# Omnibot_battery_module.net
KiCad netlist of a schematic drawn in EAGLE
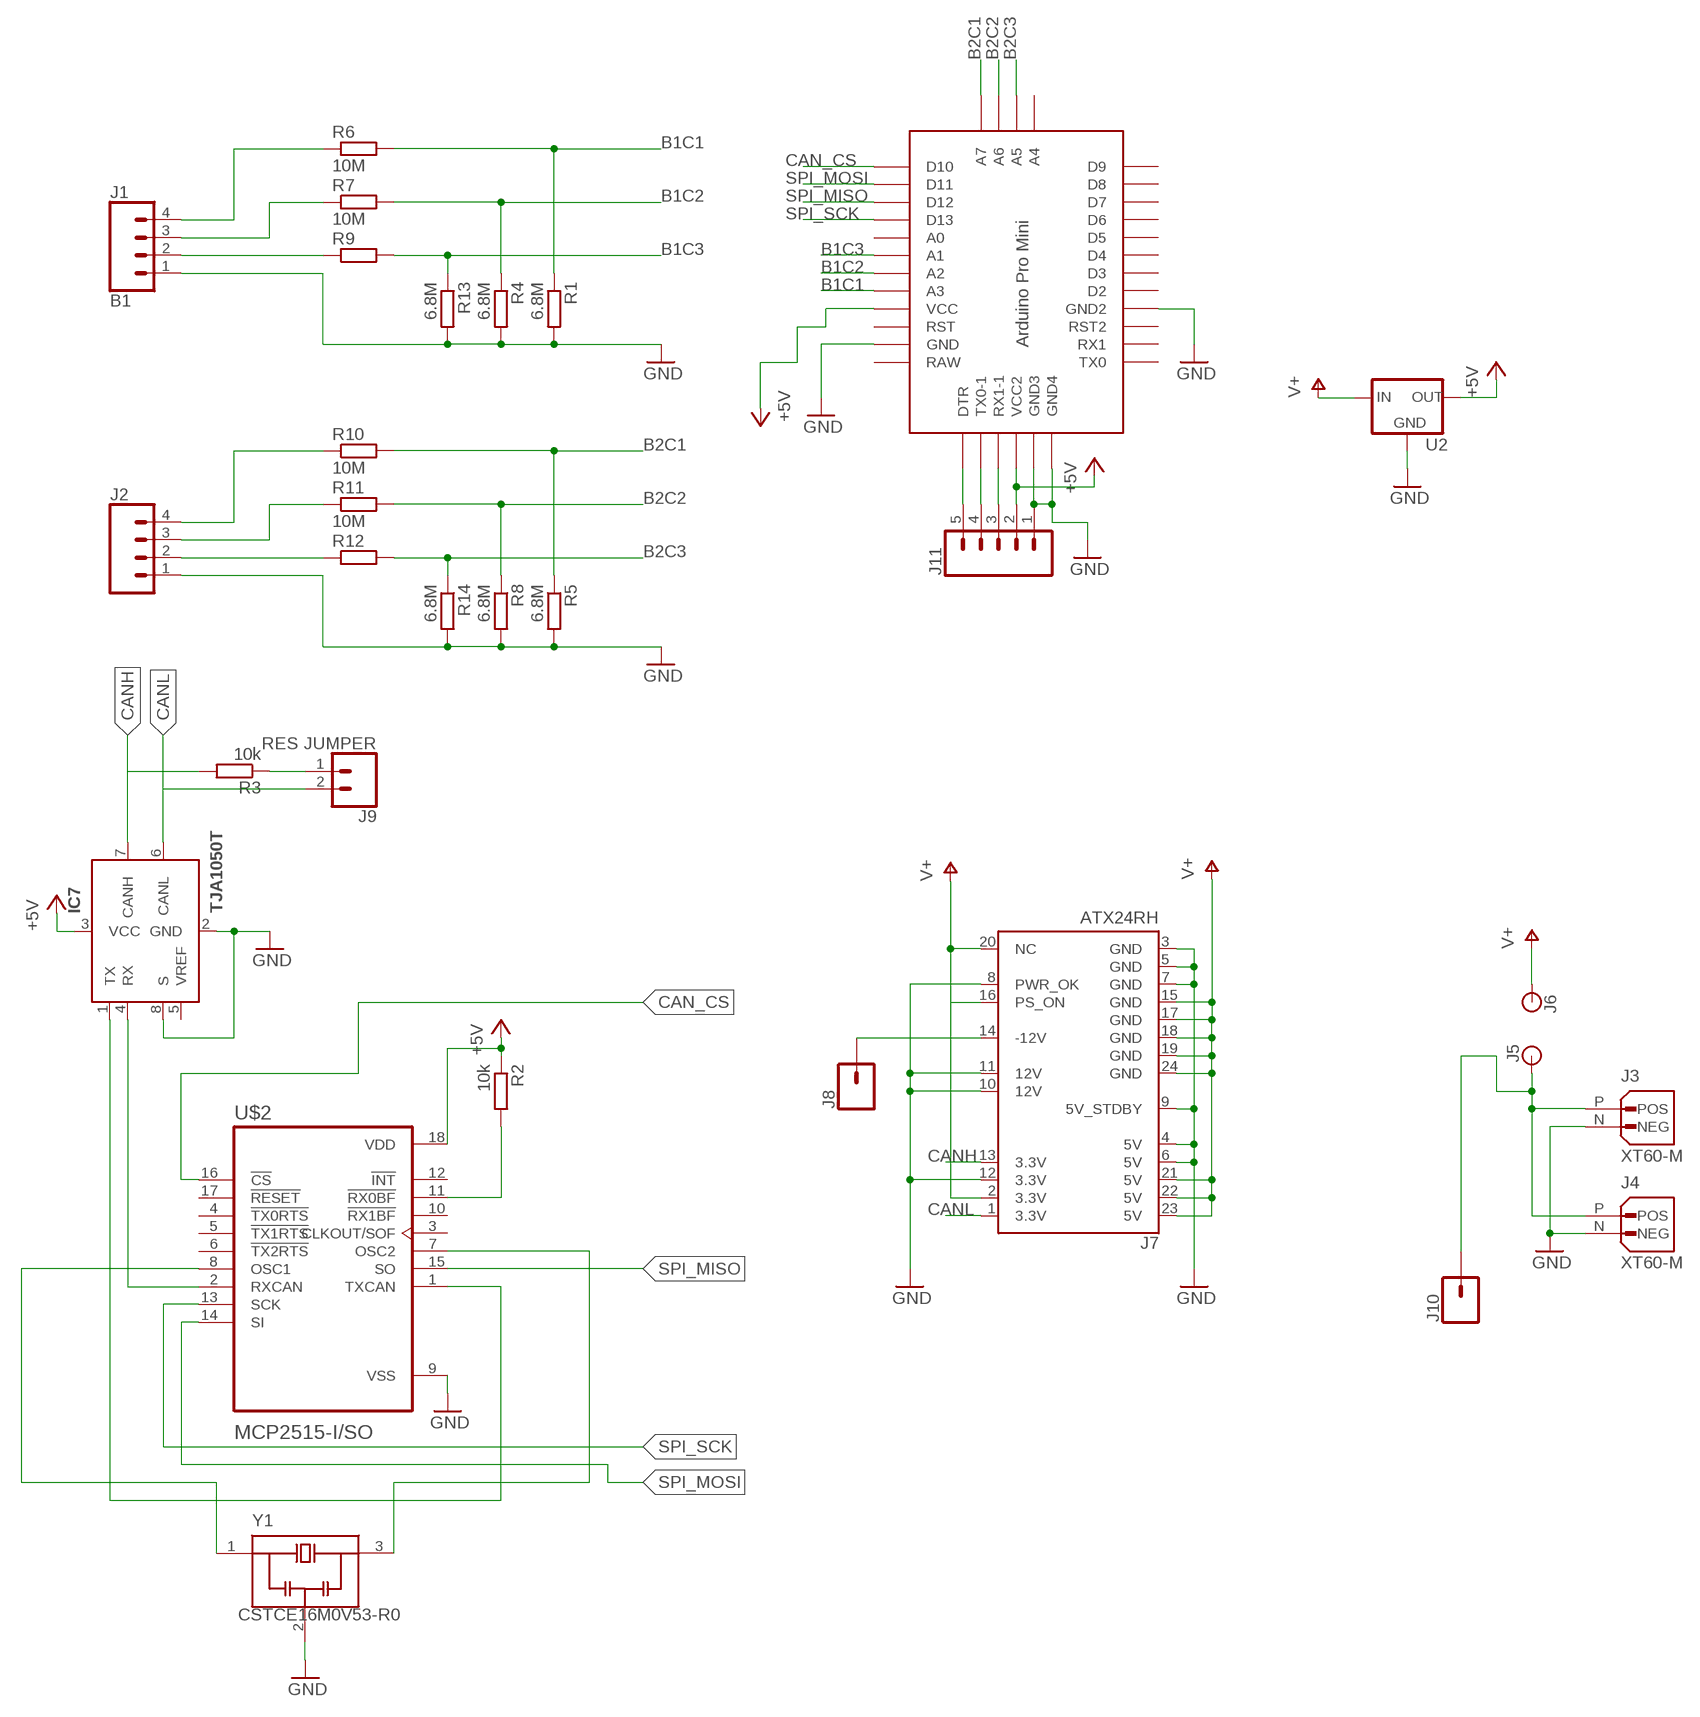
[diagram p0: schematic, sheet 1]

(export (version "E")
  (design (tool "Eeschema 10.0.6"))
  (components
    (comp (ref "IC7")
      (value "TJA1050T")
      (footprint "eagle-import:SOIC8")
      (fields (field (name "MF") "NXP"))
      (libsource (lib "eagle-import") (part "TJA1050T"))
    )
    (comp (ref "J1")
      (value "B1")
      (footprint "eagle-import:MOLEX-1X4")
      (libsource (lib "eagle-import") (part "CONN_04POLAR"))
    )
    (comp (ref "J2")
      (value "CONN_04POLAR")
      (footprint "eagle-import:MOLEX-1X4")
      (libsource (lib "eagle-import") (part "CONN_04POLAR"))
    )
    (comp (ref "J3")
      (value "XT60-M")
      (footprint "eagle-import:AMASS_XT60-M")
      (fields (field (name "MF") "AMASS"))
      (libsource (lib "eagle-import") (part "XT60-M"))
    )
    (comp (ref "J4")
      (value "XT60-M")
      (footprint "eagle-import:AMASS_XT60-M")
      (fields (field (name "MF") "AMASS"))
      (libsource (lib "eagle-import") (part "XT60-M"))
    )
    (comp (ref "J5")
      (value "BANANA_CONN")
      (footprint "eagle-import:BANANA_CONN")
      (libsource (lib "eagle-import") (part "BANANA_CONN"))
    )
    (comp (ref "J6")
      (value "BANANA_CONN")
      (footprint "eagle-import:BANANA_CONN")
      (libsource (lib "eagle-import") (part "BANANA_CONN"))
    )
    (comp (ref "J7")
      (value "ATX24RH")
      (footprint "eagle-import:ATX24_RIGHT_ANGLE")
      (libsource (lib "eagle-import") (part "ATX24RH"))
    )
    (comp (ref "J8")
      (value "CONN_01")
      (footprint "eagle-import:1X01")
      (libsource (lib "eagle-import") (part "CONN_01"))
    )
    (comp (ref "J9")
      (value "RES JUMPER")
      (footprint "eagle-import:1X02")
      (libsource (lib "eagle-import") (part "CONN_02"))
    )
    (comp (ref "J10")
      (value "CONN_01")
      (footprint "eagle-import:1X01")
      (libsource (lib "eagle-import") (part "CONN_01"))
    )
    (comp (ref "J11")
      (value "CONN_05PTH")
      (footprint "eagle-import:1X05")
      (libsource (lib "eagle-import") (part "CONN_05PTH"))
    )
    (comp (ref "R1")
      (value "6.8M")
      (footprint "eagle-import:M0805")
      (libsource (lib "eagle-import") (part "R-EU_M0805"))
    )
    (comp (ref "R2")
      (value "10k")
      (footprint "eagle-import:R0805")
      (libsource (lib "eagle-import") (part "R-EU_R0805"))
    )
    (comp (ref "R3")
      (value "10k")
      (footprint "eagle-import:R0805")
      (libsource (lib "eagle-import") (part "R-EU_R0805"))
    )
    (comp (ref "R4")
      (value "6.8M")
      (footprint "eagle-import:M0805")
      (libsource (lib "eagle-import") (part "R-EU_M0805"))
    )
    (comp (ref "R5")
      (value "6.8M")
      (footprint "eagle-import:M0805")
      (libsource (lib "eagle-import") (part "R-EU_M0805"))
    )
    (comp (ref "R6")
      (value "10M")
      (footprint "eagle-import:M0805")
      (libsource (lib "eagle-import") (part "R-EU_M0805"))
    )
    (comp (ref "R7")
      (value "10M")
      (footprint "eagle-import:M0805")
      (libsource (lib "eagle-import") (part "R-EU_M0805"))
    )
    (comp (ref "R8")
      (value "6.8M")
      (footprint "eagle-import:M0805")
      (libsource (lib "eagle-import") (part "R-EU_M0805"))
    )
    (comp (ref "R9")
      (value "10M")
      (footprint "eagle-import:M0805")
      (libsource (lib "eagle-import") (part "R-EU_M0805"))
    )
    (comp (ref "R10")
      (value "10M")
      (footprint "eagle-import:M0805")
      (libsource (lib "eagle-import") (part "R-EU_M0805"))
    )
    (comp (ref "R11")
      (value "10M")
      (footprint "eagle-import:M0805")
      (libsource (lib "eagle-import") (part "R-EU_M0805"))
    )
    (comp (ref "R12")
      (value "10M")
      (footprint "eagle-import:M0805")
      (libsource (lib "eagle-import") (part "R-EU_M0805"))
    )
    (comp (ref "R13")
      (value "6.8M")
      (footprint "eagle-import:M0805")
      (libsource (lib "eagle-import") (part "R-EU_M0805"))
    )
    (comp (ref "R14")
      (value "6.8M")
      (footprint "eagle-import:M0805")
      (libsource (lib "eagle-import") (part "R-EU_M0805"))
    )
    (comp (ref "U$1")
      (value "PRO-MINI")
      (footprint "eagle-import:PRO-MINI")
      (libsource (lib "eagle-import") (part "PRO-MINI"))
    )
    (comp (ref "U$2")
      (value "MCP2515-I/SO")
      (footprint "eagle-import:SOIC127P1030X265-18N")
      (fields (field (name "MF") "Microchip"))
      (libsource (lib "eagle-import") (part "MCP2515-I/SO"))
    )
    (comp (ref "U2")
      (value "V_REG_78XX-TO-220")
      (footprint "eagle-import:TO-220-ALT")
      (libsource (lib "eagle-import") (part "V_REG_78XX-TO-220"))
    )
    (comp (ref "Y1")
      (value "CSTCE16M0V53-R0")
      (footprint "eagle-import:OSC_CSTCE16M0V53-R0")
      (fields (field (name "MF") "Murata"))
      (libsource (lib "eagle-import") (part "CSTCE16M0V53-R0"))
    )
  )
  (nets
    (net (code "1") (name "+5V") (class "Default")
      (node (ref "IC7") (pin "3") (pinfunction "VCC_3") (pintype "input"))
      (node (ref "J11") (pin "2") (pinfunction "2_2") (pintype "passive"))
      (node (ref "R2") (pin "1") (pinfunction "1_1") (pintype "passive"))
      (node (ref "U$1") (pin "VCC") (pinfunction "VCC_VCC") (pintype "bidirectional"))
      (node (ref "U$1") (pin "VCC1") (pinfunction "VCC2_VCC1") (pintype "bidirectional"))
      (node (ref "U$2") (pin "18") (pinfunction "VDD_18") (pintype "power_in"))
      (node (ref "U2") (pin "OUT") (pinfunction "OUT_OUT") (pintype "passive"))
    )
    (net (code "2") (name "/B1C1") (class "Default")
      (node (ref "R1") (pin "1") (pinfunction "1_1") (pintype "passive"))
      (node (ref "R6") (pin "2") (pinfunction "2_2") (pintype "passive"))
      (node (ref "U$1") (pin "A3") (pinfunction "A3_A3") (pintype "bidirectional"))
    )
    (net (code "3") (name "/B1C2") (class "Default")
      (node (ref "R4") (pin "1") (pinfunction "1_1") (pintype "passive"))
      (node (ref "R7") (pin "2") (pinfunction "2_2") (pintype "passive"))
      (node (ref "U$1") (pin "A2") (pinfunction "A2_A2") (pintype "bidirectional"))
    )
    (net (code "4") (name "/B1C3") (class "Default")
      (node (ref "R13") (pin "1") (pinfunction "1_1") (pintype "passive"))
      (node (ref "R9") (pin "2") (pinfunction "2_2") (pintype "passive"))
      (node (ref "U$1") (pin "A1") (pinfunction "A1_A1") (pintype "bidirectional"))
    )
    (net (code "5") (name "/B2C1") (class "Default")
      (node (ref "R10") (pin "2") (pinfunction "2_2") (pintype "passive"))
      (node (ref "R5") (pin "1") (pinfunction "1_1") (pintype "passive"))
      (node (ref "U$1") (pin "A7") (pinfunction "A7_A7") (pintype "bidirectional"))
    )
    (net (code "6") (name "/B2C2") (class "Default")
      (node (ref "R11") (pin "2") (pinfunction "2_2") (pintype "passive"))
      (node (ref "R8") (pin "1") (pinfunction "1_1") (pintype "passive"))
      (node (ref "U$1") (pin "A6") (pinfunction "A6_A6") (pintype "bidirectional"))
    )
    (net (code "7") (name "/B2C3") (class "Default")
      (node (ref "R12") (pin "2") (pinfunction "2_2") (pintype "passive"))
      (node (ref "R14") (pin "1") (pinfunction "1_1") (pintype "passive"))
      (node (ref "U$1") (pin "A5") (pinfunction "A5_A5") (pintype "bidirectional"))
    )
    (net (code "8") (name "/RAW") (class "Default")
      (node (ref "U$1") (pin "RAW") (pinfunction "RAW_RAW") (pintype "power_in"))
    )
    (net (code "9") (name "CANH") (class "Default")
      (node (ref "IC7") (pin "7") (pinfunction "CANH_7") (pintype "bidirectional"))
      (node (ref "J7") (pin "13") (pinfunction "3.3V_13") (pintype "bidirectional"))
      (node (ref "R3") (pin "2") (pinfunction "2_2") (pintype "passive"))
    )
    (net (code "10") (name "CANL") (class "Default")
      (node (ref "IC7") (pin "6") (pinfunction "CANL_6") (pintype "bidirectional"))
      (node (ref "J7") (pin "1") (pinfunction "3.3V_1") (pintype "bidirectional"))
      (node (ref "J9") (pin "2") (pinfunction "2_2") (pintype "passive"))
    )
    (net (code "11") (name "CAN_CS") (class "Default")
      (node (ref "U$1") (pin "D10") (pinfunction "D10_D10") (pintype "bidirectional"))
      (node (ref "U$2") (pin "16") (pinfunction "~{CS}_16") (pintype "input"))
    )
    (net (code "12") (name "GND") (class "Default")
      (node (ref "IC7") (pin "2") (pinfunction "GND_2") (pintype "power_in"))
      (node (ref "IC7") (pin "8") (pinfunction "S_8") (pintype "input"))
      (node (ref "J1") (pin "1") (pinfunction "1_1") (pintype "passive"))
      (node (ref "J11") (pin "1") (pinfunction "1_1") (pintype "passive"))
      (node (ref "J2") (pin "1") (pinfunction "1_1") (pintype "passive"))
      (node (ref "J3") (pin "N") (pinfunction "NEG_N") (pintype "passive"))
      (node (ref "J4") (pin "N") (pinfunction "NEG_N") (pintype "passive"))
      (node (ref "J7") (pin "10") (pinfunction "12V_10") (pintype "bidirectional"))
      (node (ref "J7") (pin "11") (pinfunction "12V_11") (pintype "bidirectional"))
      (node (ref "J7") (pin "12") (pinfunction "3.3V_12") (pintype "bidirectional"))
      (node (ref "J7") (pin "3") (pinfunction "GND_3") (pintype "bidirectional"))
      (node (ref "J7") (pin "4") (pinfunction "5V_4") (pintype "bidirectional"))
      (node (ref "J7") (pin "5") (pinfunction "GND_5") (pintype "bidirectional"))
      (node (ref "J7") (pin "6") (pinfunction "5V_6") (pintype "bidirectional"))
      (node (ref "J7") (pin "7") (pinfunction "GND_7") (pintype "bidirectional"))
      (node (ref "J7") (pin "8") (pinfunction "PWR_OK_8") (pintype "bidirectional"))
      (node (ref "J7") (pin "9") (pinfunction "5V_STDBY_9") (pintype "bidirectional"))
      (node (ref "R1") (pin "2") (pinfunction "2_2") (pintype "passive"))
      (node (ref "R13") (pin "2") (pinfunction "2_2") (pintype "passive"))
      (node (ref "R14") (pin "2") (pinfunction "2_2") (pintype "passive"))
      (node (ref "R4") (pin "2") (pinfunction "2_2") (pintype "passive"))
      (node (ref "R5") (pin "2") (pinfunction "2_2") (pintype "passive"))
      (node (ref "R8") (pin "2") (pinfunction "2_2") (pintype "passive"))
      (node (ref "U$1") (pin "GND") (pinfunction "GND_GND") (pintype "input"))
      (node (ref "U$1") (pin "GND1") (pinfunction "GND2_GND1") (pintype "bidirectional"))
      (node (ref "U$1") (pin "GND2") (pinfunction "GND4_GND2") (pintype "bidirectional"))
      (node (ref "U$1") (pin "GND3") (pinfunction "GND3_GND3") (pintype "bidirectional"))
      (node (ref "U$2") (pin "9") (pinfunction "VSS_9") (pintype "power_in"))
      (node (ref "U2") (pin "GND") (pinfunction "GND_GND") (pintype "input"))
      (node (ref "Y1") (pin "2") (pinfunction "GND_2") (pintype "power_in"))
    )
    (net (code "13") (name "Net-(IC7-RX)") (class "Default")
      (node (ref "IC7") (pin "4") (pinfunction "RX_4") (pintype "output"))
      (node (ref "U$2") (pin "2") (pinfunction "RXCAN_2") (pintype "input"))
    )
    (net (code "14") (name "Net-(IC7-TX)") (class "Default")
      (node (ref "IC7") (pin "1") (pinfunction "TX_1") (pintype "input"))
      (node (ref "U$2") (pin "1") (pinfunction "TXCAN_1") (pintype "output"))
    )
    (net (code "15") (name "Net-(J1-Pad2)") (class "Default")
      (node (ref "J1") (pin "2") (pinfunction "2_2") (pintype "passive"))
      (node (ref "R9") (pin "1") (pinfunction "1_1") (pintype "passive"))
    )
    (net (code "16") (name "Net-(J1-Pad3)") (class "Default")
      (node (ref "J1") (pin "3") (pinfunction "3_3") (pintype "passive"))
      (node (ref "R7") (pin "1") (pinfunction "1_1") (pintype "passive"))
    )
    (net (code "17") (name "Net-(J1-Pad4)") (class "Default")
      (node (ref "J1") (pin "4") (pinfunction "4_4") (pintype "passive"))
      (node (ref "R6") (pin "1") (pinfunction "1_1") (pintype "passive"))
    )
    (net (code "18") (name "Net-(J2-Pad2)") (class "Default")
      (node (ref "J2") (pin "2") (pinfunction "2_2") (pintype "passive"))
      (node (ref "R12") (pin "1") (pinfunction "1_1") (pintype "passive"))
    )
    (net (code "19") (name "Net-(J2-Pad3)") (class "Default")
      (node (ref "J2") (pin "3") (pinfunction "3_3") (pintype "passive"))
      (node (ref "R11") (pin "1") (pinfunction "1_1") (pintype "passive"))
    )
    (net (code "20") (name "Net-(J2-Pad4)") (class "Default")
      (node (ref "J2") (pin "4") (pinfunction "4_4") (pintype "passive"))
      (node (ref "R10") (pin "1") (pinfunction "1_1") (pintype "passive"))
    )
    (net (code "21") (name "Net-(J3-POS)") (class "Default")
      (node (ref "J10") (pin "1") (pinfunction "1_1") (pintype "passive"))
      (node (ref "J3") (pin "P") (pinfunction "POS_P") (pintype "passive"))
      (node (ref "J4") (pin "P") (pinfunction "POS_P") (pintype "passive"))
      (node (ref "J5") (pin "P$1") (pinfunction "1_P$1") (pintype "passive"))
    )
    (net (code "22") (name "Net-(J7--12V)") (class "Default")
      (node (ref "J7") (pin "14") (pinfunction "-12V_14") (pintype "bidirectional"))
      (node (ref "J8") (pin "1") (pinfunction "1_1") (pintype "passive"))
    )
    (net (code "23") (name "Net-(J9-Pad1)") (class "Default")
      (node (ref "J9") (pin "1") (pinfunction "1_1") (pintype "passive"))
      (node (ref "R3") (pin "1") (pinfunction "1_1") (pintype "passive"))
    )
    (net (code "24") (name "Net-(J11-Pad3)") (class "Default")
      (node (ref "J11") (pin "3") (pinfunction "3_3") (pintype "passive"))
      (node (ref "U$1") (pin "RX1-1") (pinfunction "RX1-1_RX1-1") (pintype "bidirectional"))
    )
    (net (code "25") (name "Net-(J11-Pad4)") (class "Default")
      (node (ref "J11") (pin "4") (pinfunction "4_4") (pintype "passive"))
      (node (ref "U$1") (pin "TX0-1") (pinfunction "TX0-1_TX0-1") (pintype "bidirectional"))
    )
    (net (code "26") (name "Net-(J11-Pad5)") (class "Default")
      (node (ref "J11") (pin "5") (pinfunction "5_5") (pintype "passive"))
      (node (ref "U$1") (pin "DTR") (pinfunction "DTR_DTR") (pintype "bidirectional"))
    )
    (net (code "27") (name "Net-(U$2-OSC1)") (class "Default")
      (node (ref "U$2") (pin "8") (pinfunction "OSC1_8") (pintype "input"))
      (node (ref "Y1") (pin "1") (pinfunction "IN_1") (pintype "input"))
    )
    (net (code "28") (name "Net-(U$2-OSC2)") (class "Default")
      (node (ref "U$2") (pin "7") (pinfunction "OSC2_7") (pintype "output"))
      (node (ref "Y1") (pin "3") (pinfunction "OUT_3") (pintype "output"))
    )
    (net (code "29") (name "Net-(U$2-~{RX0BF})") (class "Default")
      (node (ref "R2") (pin "2") (pinfunction "2_2") (pintype "passive"))
      (node (ref "U$2") (pin "11") (pinfunction "~{RX0BF}_11") (pintype "output"))
    )
    (net (code "30") (name "SPI_MISO") (class "Default")
      (node (ref "U$1") (pin "D12") (pinfunction "D12_D12") (pintype "bidirectional"))
      (node (ref "U$2") (pin "15") (pinfunction "SO_15") (pintype "output"))
    )
    (net (code "31") (name "SPI_MOSI") (class "Default")
      (node (ref "U$1") (pin "D11") (pinfunction "D11_D11") (pintype "bidirectional"))
      (node (ref "U$2") (pin "14") (pinfunction "SI_14") (pintype "input"))
    )
    (net (code "32") (name "SPI_SCK") (class "Default")
      (node (ref "U$1") (pin "D13") (pinfunction "D13_D13") (pintype "bidirectional"))
      (node (ref "U$2") (pin "13") (pinfunction "SCK_13") (pintype "input"))
    )
    (net (code "33") (name "V+") (class "Default")
      (node (ref "J6") (pin "P$1") (pinfunction "1_P$1") (pintype "passive"))
      (node (ref "J7") (pin "15") (pinfunction "GND_15") (pintype "bidirectional"))
      (node (ref "J7") (pin "16") (pinfunction "PS_ON_16") (pintype "bidirectional"))
      (node (ref "J7") (pin "17") (pinfunction "GND_17") (pintype "bidirectional"))
      (node (ref "J7") (pin "18") (pinfunction "GND_18") (pintype "bidirectional"))
      (node (ref "J7") (pin "19") (pinfunction "GND_19") (pintype "bidirectional"))
      (node (ref "J7") (pin "2") (pinfunction "3.3V_2") (pintype "bidirectional"))
      (node (ref "J7") (pin "20") (pinfunction "NC_20") (pintype "bidirectional"))
      (node (ref "J7") (pin "21") (pinfunction "5V_21") (pintype "bidirectional"))
      (node (ref "J7") (pin "22") (pinfunction "5V_22") (pintype "bidirectional"))
      (node (ref "J7") (pin "23") (pinfunction "5V_23") (pintype "bidirectional"))
      (node (ref "J7") (pin "24") (pinfunction "GND_24") (pintype "bidirectional"))
      (node (ref "U2") (pin "IN") (pinfunction "IN_IN") (pintype "input"))
    )
    (net (code "34") (name "unconnected-(IC7-VREF-Pad5)") (class "Default")
      (node (ref "IC7") (pin "5") (pinfunction "VREF_5") (pintype "output"))
    )
    (net (code "35") (name "unconnected-(U$1-PadA0)") (class "Default")
      (node (ref "U$1") (pin "A0") (pinfunction "A0_A0") (pintype "bidirectional"))
    )
    (net (code "36") (name "unconnected-(U$1-PadA4)") (class "Default")
      (node (ref "U$1") (pin "A4") (pinfunction "A4_A4") (pintype "bidirectional"))
    )
    (net (code "37") (name "unconnected-(U$1-PadD2)") (class "Default")
      (node (ref "U$1") (pin "D2") (pinfunction "D2_D2") (pintype "bidirectional"))
    )
    (net (code "38") (name "unconnected-(U$1-PadD3)") (class "Default")
      (node (ref "U$1") (pin "D3") (pinfunction "D3_D3") (pintype "bidirectional"))
    )
    (net (code "39") (name "unconnected-(U$1-PadD4)") (class "Default")
      (node (ref "U$1") (pin "D4") (pinfunction "D4_D4") (pintype "bidirectional"))
    )
    (net (code "40") (name "unconnected-(U$1-PadD5)") (class "Default")
      (node (ref "U$1") (pin "D5") (pinfunction "D5_D5") (pintype "bidirectional"))
    )
    (net (code "41") (name "unconnected-(U$1-PadD6)") (class "Default")
      (node (ref "U$1") (pin "D6") (pinfunction "D6_D6") (pintype "bidirectional"))
    )
    (net (code "42") (name "unconnected-(U$1-PadD7)") (class "Default")
      (node (ref "U$1") (pin "D7") (pinfunction "D7_D7") (pintype "bidirectional"))
    )
    (net (code "43") (name "unconnected-(U$1-PadD8)") (class "Default")
      (node (ref "U$1") (pin "D8") (pinfunction "D8_D8") (pintype "bidirectional"))
    )
    (net (code "44") (name "unconnected-(U$1-PadD9)") (class "Default")
      (node (ref "U$1") (pin "D9") (pinfunction "D9_D9") (pintype "bidirectional"))
    )
    (net (code "45") (name "unconnected-(U$1-PadRST)") (class "Default")
      (node (ref "U$1") (pin "RST") (pinfunction "RST_RST") (pintype "bidirectional"))
    )
    (net (code "46") (name "unconnected-(U$1-PadRX1)") (class "Default")
      (node (ref "U$1") (pin "RX1") (pinfunction "RX1_RX1") (pintype "bidirectional"))
    )
    (net (code "47") (name "unconnected-(U$1-PadTX0)") (class "Default")
      (node (ref "U$1") (pin "TX0") (pinfunction "TX0_TX0") (pintype "bidirectional"))
    )
    (net (code "48") (name "unconnected-(U$1-RST2-PadRST1)") (class "Default")
      (node (ref "U$1") (pin "RST1") (pinfunction "RST2_RST1") (pintype "bidirectional"))
    )
    (net (code "49") (name "unconnected-(U$2-CLKOUT{slash}SOF-Pad3)") (class "Default")
      (node (ref "U$2") (pin "3") (pinfunction "CLKOUT/SOF_3") (pintype "output"))
    )
    (net (code "50") (name "unconnected-(U$2-~{INT}-Pad12)") (class "Default")
      (node (ref "U$2") (pin "12") (pinfunction "~{INT}_12") (pintype "output"))
    )
    (net (code "51") (name "unconnected-(U$2-~{RESET}-Pad17)") (class "Default")
      (node (ref "U$2") (pin "17") (pinfunction "~{RESET}_17") (pintype "input"))
    )
    (net (code "52") (name "unconnected-(U$2-~{RX1BF}-Pad10)") (class "Default")
      (node (ref "U$2") (pin "10") (pinfunction "~{RX1BF}_10") (pintype "output"))
    )
    (net (code "53") (name "unconnected-(U$2-~{TX0RTS}-Pad4)") (class "Default")
      (node (ref "U$2") (pin "4") (pinfunction "~{TX0RTS}_4") (pintype "input"))
    )
    (net (code "54") (name "unconnected-(U$2-~{TX1RTS}-Pad5)") (class "Default")
      (node (ref "U$2") (pin "5") (pinfunction "~{TX1RTS}_5") (pintype "input"))
    )
    (net (code "55") (name "unconnected-(U$2-~{TX2RTS}-Pad6)") (class "Default")
      (node (ref "U$2") (pin "6") (pinfunction "~{TX2RTS}_6") (pintype "input"))
    )
  )
)
